# SCH_Szachy_2025-08-29.net
KiCad netlist of a schematic drawn in EasyEDA
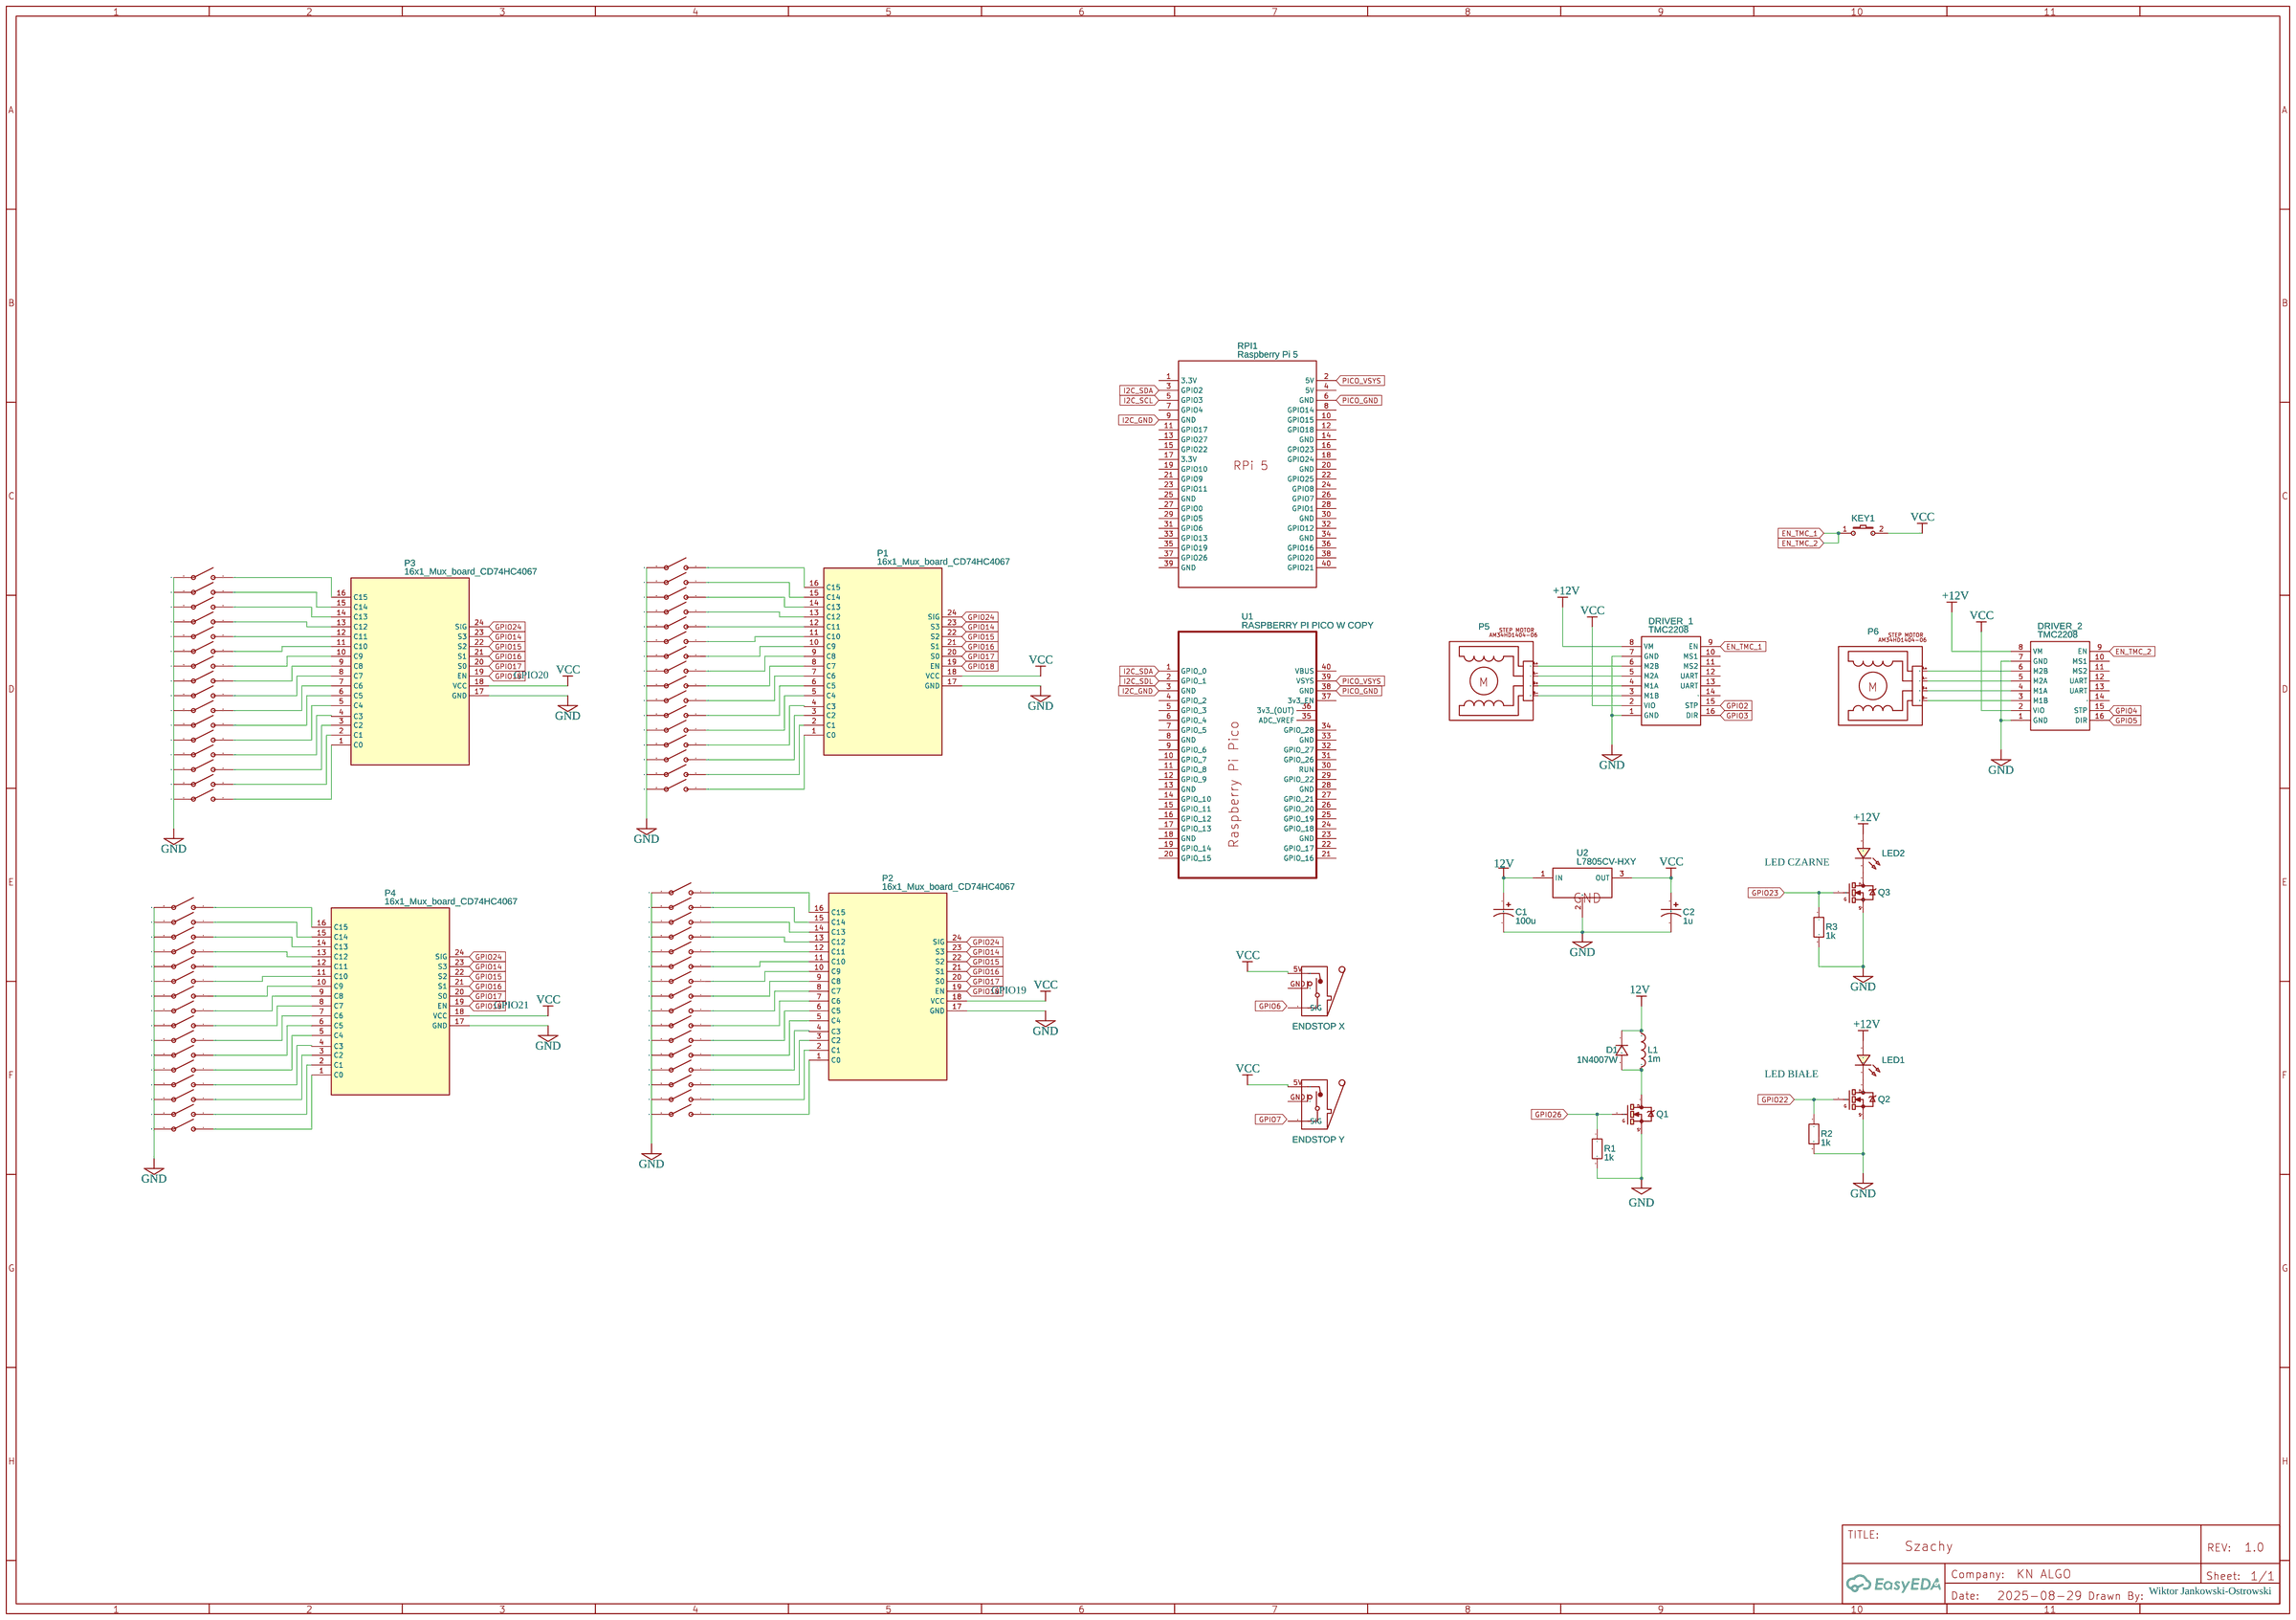
[diagram p0: schematic sheet]

(export (version "E")
  (design (tool "Eeschema 10.0.6"))
  (components
    (comp (ref "C1") (value "100u") (libsource (lib "") (part "C_Tan_SMD_A_US")))
    (comp (ref "C2") (value "1u") (libsource (lib "") (part "C_Tan_SMD_A_US")))
    (comp (ref "D1")
      (value "1N4007W")
      (fields (field (name "Manufacturer") "BLUE ROCKET"))
      (libsource (lib "") (part "1N4007W"))
    )
    (comp (ref "DIP1")
      (value "switch1")
      (fields (field (name "Manufacturer Part") "DIP switchEI-08") (field (name "Manufacturer") "DIP"))
      (libsource (lib "") (part "switch1"))
    )
    (comp (ref "DIP2")
      (value "switch1")
      (fields (field (name "Manufacturer Part") "DIP switchEI-08") (field (name "Manufacturer") "DIP"))
      (libsource (lib "") (part "switch1"))
    )
    (comp (ref "DIP3")
      (value "switch1")
      (fields (field (name "Manufacturer Part") "DIP switchEI-08") (field (name "Manufacturer") "DIP"))
      (libsource (lib "") (part "switch1"))
    )
    (comp (ref "DIP4")
      (value "switch1")
      (fields (field (name "Manufacturer Part") "DIP switchEI-08") (field (name "Manufacturer") "DIP"))
      (libsource (lib "") (part "switch1"))
    )
    (comp (ref "DIP5")
      (value "switch1")
      (fields (field (name "Manufacturer Part") "DIP switchEI-08") (field (name "Manufacturer") "DIP"))
      (libsource (lib "") (part "switch1"))
    )
    (comp (ref "DIP6")
      (value "switch1")
      (fields (field (name "Manufacturer Part") "DIP switchEI-08") (field (name "Manufacturer") "DIP"))
      (libsource (lib "") (part "switch1"))
    )
    (comp (ref "DIP7")
      (value "switch1")
      (fields (field (name "Manufacturer Part") "DIP switchEI-08") (field (name "Manufacturer") "DIP"))
      (libsource (lib "") (part "switch1"))
    )
    (comp (ref "DIP8")
      (value "switch1")
      (fields (field (name "Manufacturer Part") "DIP switchEI-08") (field (name "Manufacturer") "DIP"))
      (libsource (lib "") (part "switch1"))
    )
    (comp (ref "DIP9")
      (value "switch1")
      (fields (field (name "Manufacturer Part") "DIP switchEI-08") (field (name "Manufacturer") "DIP"))
      (libsource (lib "") (part "switch1"))
    )
    (comp (ref "DIP10")
      (value "switch1")
      (fields (field (name "Manufacturer Part") "DIP switchEI-08") (field (name "Manufacturer") "DIP"))
      (libsource (lib "") (part "switch1"))
    )
    (comp (ref "DIP11")
      (value "switch1")
      (fields (field (name "Manufacturer Part") "DIP switchEI-08") (field (name "Manufacturer") "DIP"))
      (libsource (lib "") (part "switch1"))
    )
    (comp (ref "DIP12")
      (value "switch1")
      (fields (field (name "Manufacturer Part") "DIP switchEI-08") (field (name "Manufacturer") "DIP"))
      (libsource (lib "") (part "switch1"))
    )
    (comp (ref "DIP13")
      (value "switch1")
      (fields (field (name "Manufacturer Part") "DIP switchEI-08") (field (name "Manufacturer") "DIP"))
      (libsource (lib "") (part "switch1"))
    )
    (comp (ref "DIP14")
      (value "switch1")
      (fields (field (name "Manufacturer Part") "DIP switchEI-08") (field (name "Manufacturer") "DIP"))
      (libsource (lib "") (part "switch1"))
    )
    (comp (ref "DIP15")
      (value "switch1")
      (fields (field (name "Manufacturer Part") "DIP switchEI-08") (field (name "Manufacturer") "DIP"))
      (libsource (lib "") (part "switch1"))
    )
    (comp (ref "DIP16")
      (value "switch1")
      (fields (field (name "Manufacturer Part") "DIP switchEI-08") (field (name "Manufacturer") "DIP"))
      (libsource (lib "") (part "switch1"))
    )
    (comp (ref "DIP17")
      (value "switch1")
      (fields (field (name "Manufacturer Part") "DIP switchEI-08") (field (name "Manufacturer") "DIP"))
      (libsource (lib "") (part "switch1"))
    )
    (comp (ref "DIP18")
      (value "switch1")
      (fields (field (name "Manufacturer Part") "DIP switchEI-08") (field (name "Manufacturer") "DIP"))
      (libsource (lib "") (part "switch1"))
    )
    (comp (ref "DIP19")
      (value "switch1")
      (fields (field (name "Manufacturer Part") "DIP switchEI-08") (field (name "Manufacturer") "DIP"))
      (libsource (lib "") (part "switch1"))
    )
    (comp (ref "DIP20")
      (value "switch1")
      (fields (field (name "Manufacturer Part") "DIP switchEI-08") (field (name "Manufacturer") "DIP"))
      (libsource (lib "") (part "switch1"))
    )
    (comp (ref "DIP21")
      (value "switch1")
      (fields (field (name "Manufacturer Part") "DIP switchEI-08") (field (name "Manufacturer") "DIP"))
      (libsource (lib "") (part "switch1"))
    )
    (comp (ref "DIP22")
      (value "switch1")
      (fields (field (name "Manufacturer Part") "DIP switchEI-08") (field (name "Manufacturer") "DIP"))
      (libsource (lib "") (part "switch1"))
    )
    (comp (ref "DIP23")
      (value "switch1")
      (fields (field (name "Manufacturer Part") "DIP switchEI-08") (field (name "Manufacturer") "DIP"))
      (libsource (lib "") (part "switch1"))
    )
    (comp (ref "DIP24")
      (value "switch1")
      (fields (field (name "Manufacturer Part") "DIP switchEI-08") (field (name "Manufacturer") "DIP"))
      (libsource (lib "") (part "switch1"))
    )
    (comp (ref "DIP25")
      (value "switch1")
      (fields (field (name "Manufacturer Part") "DIP switchEI-08") (field (name "Manufacturer") "DIP"))
      (libsource (lib "") (part "switch1"))
    )
    (comp (ref "DIP26")
      (value "switch1")
      (fields (field (name "Manufacturer Part") "DIP switchEI-08") (field (name "Manufacturer") "DIP"))
      (libsource (lib "") (part "switch1"))
    )
    (comp (ref "DIP27")
      (value "switch1")
      (fields (field (name "Manufacturer Part") "DIP switchEI-08") (field (name "Manufacturer") "DIP"))
      (libsource (lib "") (part "switch1"))
    )
    (comp (ref "DIP28")
      (value "switch1")
      (fields (field (name "Manufacturer Part") "DIP switchEI-08") (field (name "Manufacturer") "DIP"))
      (libsource (lib "") (part "switch1"))
    )
    (comp (ref "DIP29")
      (value "switch1")
      (fields (field (name "Manufacturer Part") "DIP switchEI-08") (field (name "Manufacturer") "DIP"))
      (libsource (lib "") (part "switch1"))
    )
    (comp (ref "DIP30")
      (value "switch1")
      (fields (field (name "Manufacturer Part") "DIP switchEI-08") (field (name "Manufacturer") "DIP"))
      (libsource (lib "") (part "switch1"))
    )
    (comp (ref "DIP31")
      (value "switch1")
      (fields (field (name "Manufacturer Part") "DIP switchEI-08") (field (name "Manufacturer") "DIP"))
      (libsource (lib "") (part "switch1"))
    )
    (comp (ref "DIP32")
      (value "switch1")
      (fields (field (name "Manufacturer Part") "DIP switchEI-08") (field (name "Manufacturer") "DIP"))
      (libsource (lib "") (part "switch1"))
    )
    (comp (ref "DIP33")
      (value "switch1")
      (fields (field (name "Manufacturer Part") "DIP switchEI-08") (field (name "Manufacturer") "DIP"))
      (libsource (lib "") (part "switch1"))
    )
    (comp (ref "DIP34")
      (value "switch1")
      (fields (field (name "Manufacturer Part") "DIP switchEI-08") (field (name "Manufacturer") "DIP"))
      (libsource (lib "") (part "switch1"))
    )
    (comp (ref "DIP35")
      (value "switch1")
      (fields (field (name "Manufacturer Part") "DIP switchEI-08") (field (name "Manufacturer") "DIP"))
      (libsource (lib "") (part "switch1"))
    )
    (comp (ref "DIP36")
      (value "switch1")
      (fields (field (name "Manufacturer Part") "DIP switchEI-08") (field (name "Manufacturer") "DIP"))
      (libsource (lib "") (part "switch1"))
    )
    (comp (ref "DIP37")
      (value "switch1")
      (fields (field (name "Manufacturer Part") "DIP switchEI-08") (field (name "Manufacturer") "DIP"))
      (libsource (lib "") (part "switch1"))
    )
    (comp (ref "DIP38")
      (value "switch1")
      (fields (field (name "Manufacturer Part") "DIP switchEI-08") (field (name "Manufacturer") "DIP"))
      (libsource (lib "") (part "switch1"))
    )
    (comp (ref "DIP39")
      (value "switch1")
      (fields (field (name "Manufacturer Part") "DIP switchEI-08") (field (name "Manufacturer") "DIP"))
      (libsource (lib "") (part "switch1"))
    )
    (comp (ref "DIP40")
      (value "switch1")
      (fields (field (name "Manufacturer Part") "DIP switchEI-08") (field (name "Manufacturer") "DIP"))
      (libsource (lib "") (part "switch1"))
    )
    (comp (ref "DIP41")
      (value "switch1")
      (fields (field (name "Manufacturer Part") "DIP switchEI-08") (field (name "Manufacturer") "DIP"))
      (libsource (lib "") (part "switch1"))
    )
    (comp (ref "DIP42")
      (value "switch1")
      (fields (field (name "Manufacturer Part") "DIP switchEI-08") (field (name "Manufacturer") "DIP"))
      (libsource (lib "") (part "switch1"))
    )
    (comp (ref "DIP43")
      (value "switch1")
      (fields (field (name "Manufacturer Part") "DIP switchEI-08") (field (name "Manufacturer") "DIP"))
      (libsource (lib "") (part "switch1"))
    )
    (comp (ref "DIP44")
      (value "switch1")
      (fields (field (name "Manufacturer Part") "DIP switchEI-08") (field (name "Manufacturer") "DIP"))
      (libsource (lib "") (part "switch1"))
    )
    (comp (ref "DIP45")
      (value "switch1")
      (fields (field (name "Manufacturer Part") "DIP switchEI-08") (field (name "Manufacturer") "DIP"))
      (libsource (lib "") (part "switch1"))
    )
    (comp (ref "DIP46")
      (value "switch1")
      (fields (field (name "Manufacturer Part") "DIP switchEI-08") (field (name "Manufacturer") "DIP"))
      (libsource (lib "") (part "switch1"))
    )
    (comp (ref "DIP47")
      (value "switch1")
      (fields (field (name "Manufacturer Part") "DIP switchEI-08") (field (name "Manufacturer") "DIP"))
      (libsource (lib "") (part "switch1"))
    )
    (comp (ref "DIP48")
      (value "switch1")
      (fields (field (name "Manufacturer Part") "DIP switchEI-08") (field (name "Manufacturer") "DIP"))
      (libsource (lib "") (part "switch1"))
    )
    (comp (ref "DIP49")
      (value "switch1")
      (fields (field (name "Manufacturer Part") "DIP switchEI-08") (field (name "Manufacturer") "DIP"))
      (libsource (lib "") (part "switch1"))
    )
    (comp (ref "DIP50")
      (value "switch1")
      (fields (field (name "Manufacturer Part") "DIP switchEI-08") (field (name "Manufacturer") "DIP"))
      (libsource (lib "") (part "switch1"))
    )
    (comp (ref "DIP51")
      (value "switch1")
      (fields (field (name "Manufacturer Part") "DIP switchEI-08") (field (name "Manufacturer") "DIP"))
      (libsource (lib "") (part "switch1"))
    )
    (comp (ref "DIP52")
      (value "switch1")
      (fields (field (name "Manufacturer Part") "DIP switchEI-08") (field (name "Manufacturer") "DIP"))
      (libsource (lib "") (part "switch1"))
    )
    (comp (ref "DIP53")
      (value "switch1")
      (fields (field (name "Manufacturer Part") "DIP switchEI-08") (field (name "Manufacturer") "DIP"))
      (libsource (lib "") (part "switch1"))
    )
    (comp (ref "DIP54")
      (value "switch1")
      (fields (field (name "Manufacturer Part") "DIP switchEI-08") (field (name "Manufacturer") "DIP"))
      (libsource (lib "") (part "switch1"))
    )
    (comp (ref "DIP55")
      (value "switch1")
      (fields (field (name "Manufacturer Part") "DIP switchEI-08") (field (name "Manufacturer") "DIP"))
      (libsource (lib "") (part "switch1"))
    )
    (comp (ref "DIP56")
      (value "switch1")
      (fields (field (name "Manufacturer Part") "DIP switchEI-08") (field (name "Manufacturer") "DIP"))
      (libsource (lib "") (part "switch1"))
    )
    (comp (ref "DIP57")
      (value "switch1")
      (fields (field (name "Manufacturer Part") "DIP switchEI-08") (field (name "Manufacturer") "DIP"))
      (libsource (lib "") (part "switch1"))
    )
    (comp (ref "DIP58")
      (value "switch1")
      (fields (field (name "Manufacturer Part") "DIP switchEI-08") (field (name "Manufacturer") "DIP"))
      (libsource (lib "") (part "switch1"))
    )
    (comp (ref "DIP59")
      (value "switch1")
      (fields (field (name "Manufacturer Part") "DIP switchEI-08") (field (name "Manufacturer") "DIP"))
      (libsource (lib "") (part "switch1"))
    )
    (comp (ref "DIP60")
      (value "switch1")
      (fields (field (name "Manufacturer Part") "DIP switchEI-08") (field (name "Manufacturer") "DIP"))
      (libsource (lib "") (part "switch1"))
    )
    (comp (ref "DIP61")
      (value "switch1")
      (fields (field (name "Manufacturer Part") "DIP switchEI-08") (field (name "Manufacturer") "DIP"))
      (libsource (lib "") (part "switch1"))
    )
    (comp (ref "DIP62")
      (value "switch1")
      (fields (field (name "Manufacturer Part") "DIP switchEI-08") (field (name "Manufacturer") "DIP"))
      (libsource (lib "") (part "switch1"))
    )
    (comp (ref "DIP63")
      (value "switch1")
      (fields (field (name "Manufacturer Part") "DIP switchEI-08") (field (name "Manufacturer") "DIP"))
      (libsource (lib "") (part "switch1"))
    )
    (comp (ref "DIP64")
      (value "switch1")
      (fields (field (name "Manufacturer Part") "DIP switchEI-08") (field (name "Manufacturer") "DIP"))
      (libsource (lib "") (part "switch1"))
    )
    (comp (ref "DRIVER_1") (value "TMC2208") (libsource (lib "") (part "TMC2208")))
    (comp (ref "DRIVER_2") (value "TMC2208") (libsource (lib "") (part "TMC2208")))
    (comp (ref "ESTP_FU1") (value "ENDSTOP X") (libsource (lib "") (part "EndStop")))
    (comp (ref "ESTP_FU2") (value "ENDSTOP Y") (libsource (lib "") (part "EndStop")))
    (comp (ref "KEY1")
      (value "K2-3.6×6.1_SMD")
      (fields (field (name "Manufacturer Part") "K2-1107ST-A4SW-06"))
      (libsource (lib "") (part "K2-3.6×6.1_SMD"))
    )
    (comp (ref "L1") (value "1m") (libsource (lib "") (part "L0603_US")))
    (comp (ref "LED1")
      (value "LED-0603_R")
      (fields
        (field (name "Manufacturer Part") "19-217/R6C-AL1M2VY/3T")
        (field (name "Manufacturer") "EVERLIGHT(台湾亿光)")
      )
      (libsource (lib "") (part "LED-0603_R"))
    )
    (comp (ref "LED2")
      (value "LED-0603_R")
      (fields
        (field (name "Manufacturer Part") "19-217/R6C-AL1M2VY/3T")
        (field (name "Manufacturer") "EVERLIGHT(台湾亿光)")
      )
      (libsource (lib "") (part "LED-0603_R"))
    )
    (comp (ref "P1")
      (value "16x1_Mux_board_CD74HC4067")
      (libsource (lib "") (part "16x1_Mux_board_CD74HC4067"))
    )
    (comp (ref "P2")
      (value "16x1_Mux_board_CD74HC4067")
      (libsource (lib "") (part "16x1_Mux_board_CD74HC4067"))
    )
    (comp (ref "P3")
      (value "16x1_Mux_board_CD74HC4067")
      (libsource (lib "") (part "16x1_Mux_board_CD74HC4067"))
    )
    (comp (ref "P4")
      (value "16x1_Mux_board_CD74HC4067")
      (libsource (lib "") (part "16x1_Mux_board_CD74HC4067"))
    )
    (comp (ref "P5")
      (value "STEPPER MOTOR AM34HD1404-06")
      (fields
        (field (name "Manufacturer Part") "Header-Male-2.54_1x6")
        (field (name "Manufacturer") "BOOMELE")
      )
      (libsource (lib "") (part "STEPPER MOTOR AM34HD1404-06"))
    )
    (comp (ref "P6")
      (value "STEPPER MOTOR AM34HD1404-06")
      (fields
        (field (name "Manufacturer Part") "Header-Male-2.54_1x6")
        (field (name "Manufacturer") "BOOMELE")
      )
      (libsource (lib "") (part "STEPPER MOTOR AM34HD1404-06"))
    )
    (comp (ref "Q1") (value "MOSFET-NCHANNELFDD8780") (libsource (lib "") (part "MOSFET-NCHANNELFDD8780")))
    (comp (ref "Q2") (value "MOSFET-NCHANNELFDD8780") (libsource (lib "") (part "MOSFET-NCHANNELFDD8780")))
    (comp (ref "Q3") (value "MOSFET-NCHANNELFDD8780") (libsource (lib "") (part "MOSFET-NCHANNELFDD8780")))
    (comp (ref "R1") (value "1k") (libsource (lib "") (part "R_0603_EU")))
    (comp (ref "R2") (value "1k") (libsource (lib "") (part "R_0603_EU")))
    (comp (ref "R3") (value "1k") (libsource (lib "") (part "R_0603_EU")))
    (comp (ref "RPI1")
      (value "Raspberry Pi 5")
      (fields (field (name "Manufacturer") "Raspberry Pi 5 4GB"))
      (libsource (lib "") (part "Raspberry Pi 5"))
    )
    (comp (ref "U1")
      (value "RASPBERRY PI PICO W COPY")
      (libsource (lib "") (part "RASPBERRY PI PICO W COPY"))
    )
    (comp (ref "U2")
      (value "L7805CV-HXY")
      (fields (field (name "Manufacturer") "HXY MOSFET(华轩阳电子)"))
      (libsource (lib "") (part "L7805CV-HXY"))
    )
  )
  (nets
    (net (code "1") (name "+12V") (class "Default")
      (node (ref "DRIVER_1") (pin "8") (pinfunction "VM_8") (pintype "unspecified"))
      (node (ref "DRIVER_2") (pin "8") (pinfunction "VM_8") (pintype "unspecified"))
      (node (ref "LED1") (pin "1") (pinfunction "1_1") (pintype "unspecified"))
      (node (ref "LED2") (pin "1") (pinfunction "1_1") (pintype "unspecified"))
    )
    (net (code "2") (name "12V") (class "Default")
      (node (ref "C1") (pin "1") (pinfunction "1_1") (pintype "unspecified"))
      (node (ref "D1") (pin "1") (pinfunction "1_1") (pintype "unspecified"))
      (node (ref "L1") (pin "1") (pinfunction "1_1") (pintype "unspecified"))
      (node (ref "U2") (pin "1") (pinfunction "IN_1") (pintype "passive"))
    )
    (net (code "3") (name "EN_TMC_1") (class "Default")
      (node (ref "DRIVER_1") (pin "9") (pinfunction "EN_9") (pintype "unspecified"))
      (node (ref "DRIVER_2") (pin "9") (pinfunction "EN_9") (pintype "unspecified"))
      (node (ref "KEY1") (pin "1") (pinfunction "1_1") (pintype "unspecified"))
    )
    (net (code "4") (name "GND") (class "Default")
      (node (ref "C1") (pin "2") (pinfunction "2_2") (pintype "unspecified"))
      (node (ref "C2") (pin "2") (pinfunction "2_2") (pintype "unspecified"))
      (node (ref "DRIVER_1") (pin "1") (pinfunction "GND_1") (pintype "unspecified"))
      (node (ref "DRIVER_1") (pin "7") (pinfunction "GND_7") (pintype "unspecified"))
      (node (ref "DRIVER_2") (pin "1") (pinfunction "GND_1") (pintype "unspecified"))
      (node (ref "DRIVER_2") (pin "7") (pinfunction "GND_7") (pintype "unspecified"))
      (node (ref "P1") (pin "17") (pinfunction "GND_17") (pintype "unspecified"))
      (node (ref "P2") (pin "17") (pinfunction "GND_17") (pintype "unspecified"))
      (node (ref "P3") (pin "17") (pinfunction "GND_17") (pintype "unspecified"))
      (node (ref "P4") (pin "17") (pinfunction "GND_17") (pintype "unspecified"))
      (node (ref "Q1") (pin "3") (pinfunction "S_3") (pintype "unspecified"))
      (node (ref "Q2") (pin "3") (pinfunction "S_3") (pintype "unspecified"))
      (node (ref "Q3") (pin "3") (pinfunction "S_3") (pintype "unspecified"))
      (node (ref "R1") (pin "2") (pinfunction "2_2") (pintype "unspecified"))
      (node (ref "R2") (pin "2") (pinfunction "2_2") (pintype "unspecified"))
      (node (ref "R3") (pin "2") (pinfunction "2_2") (pintype "unspecified"))
      (node (ref "U2") (pin "2") (pinfunction "GND_2") (pintype "passive"))
    )
    (net (code "5") (name "GPIO2") (class "Default")
      (node (ref "DRIVER_1") (pin "15") (pinfunction "STP_15") (pintype "unspecified"))
    )
    (net (code "6") (name "GPIO3") (class "Default")
      (node (ref "DRIVER_1") (pin "16") (pinfunction "DIR_16") (pintype "unspecified"))
    )
    (net (code "7") (name "GPIO4") (class "Default")
      (node (ref "DRIVER_2") (pin "15") (pinfunction "STP_15") (pintype "unspecified"))
    )
    (net (code "8") (name "GPIO5") (class "Default")
      (node (ref "DRIVER_2") (pin "16") (pinfunction "DIR_16") (pintype "unspecified"))
    )
    (net (code "11") (name "GPIO14") (class "Default")
      (node (ref "P1") (pin "23") (pinfunction "S3_23") (pintype "unspecified"))
      (node (ref "P2") (pin "23") (pinfunction "S3_23") (pintype "unspecified"))
      (node (ref "P3") (pin "23") (pinfunction "S3_23") (pintype "unspecified"))
      (node (ref "P4") (pin "23") (pinfunction "S3_23") (pintype "unspecified"))
    )
    (net (code "12") (name "GPIO15") (class "Default")
      (node (ref "P1") (pin "22") (pinfunction "S2_22") (pintype "unspecified"))
      (node (ref "P2") (pin "22") (pinfunction "S2_22") (pintype "unspecified"))
      (node (ref "P3") (pin "22") (pinfunction "S2_22") (pintype "unspecified"))
      (node (ref "P4") (pin "22") (pinfunction "S2_22") (pintype "unspecified"))
    )
    (net (code "13") (name "GPIO16") (class "Default")
      (node (ref "P1") (pin "21") (pinfunction "S1_21") (pintype "unspecified"))
      (node (ref "P2") (pin "21") (pinfunction "S1_21") (pintype "unspecified"))
      (node (ref "P3") (pin "21") (pinfunction "S1_21") (pintype "unspecified"))
      (node (ref "P4") (pin "21") (pinfunction "S1_21") (pintype "unspecified"))
    )
    (net (code "14") (name "GPIO17") (class "Default")
      (node (ref "P1") (pin "20") (pinfunction "S0_20") (pintype "unspecified"))
      (node (ref "P2") (pin "20") (pinfunction "S0_20") (pintype "unspecified"))
      (node (ref "P3") (pin "20") (pinfunction "S0_20") (pintype "unspecified"))
      (node (ref "P4") (pin "20") (pinfunction "S0_20") (pintype "unspecified"))
    )
    (net (code "15") (name "GPIO18") (class "Default")
      (node (ref "P1") (pin "19") (pinfunction "EN_19") (pintype "unspecified"))
      (node (ref "P2") (pin "19") (pinfunction "EN_19") (pintype "unspecified"))
      (node (ref "P3") (pin "19") (pinfunction "EN_19") (pintype "unspecified"))
      (node (ref "P4") (pin "19") (pinfunction "EN_19") (pintype "unspecified"))
    )
    (net (code "16") (name "GPIO22") (class "Default")
      (node (ref "Q2") (pin "1") (pinfunction "G_1") (pintype "unspecified"))
      (node (ref "R2") (pin "1") (pinfunction "1_1") (pintype "unspecified"))
    )
    (net (code "17") (name "GPIO23") (class "Default")
      (node (ref "Q3") (pin "1") (pinfunction "G_1") (pintype "unspecified"))
      (node (ref "R3") (pin "1") (pinfunction "1_1") (pintype "unspecified"))
    )
    (net (code "18") (name "GPIO24") (class "Default")
      (node (ref "P1") (pin "24") (pinfunction "SIG_24") (pintype "unspecified"))
      (node (ref "P2") (pin "24") (pinfunction "SIG_24") (pintype "unspecified"))
      (node (ref "P3") (pin "24") (pinfunction "SIG_24") (pintype "unspecified"))
      (node (ref "P4") (pin "24") (pinfunction "SIG_24") (pintype "unspecified"))
    )
    (net (code "19") (name "GPIO26") (class "Default")
      (node (ref "Q1") (pin "1") (pinfunction "G_1") (pintype "unspecified"))
      (node (ref "R1") (pin "1") (pinfunction "1_1") (pintype "unspecified"))
    )
    (net (code "20") (name "I2C_GND") (class "Default")
      (node (ref "RPI1") (pin "9") (pinfunction "GND_9") (pintype "unspecified"))
      (node (ref "U1") (pin "3") (pinfunction "GND_3") (pintype "unspecified"))
    )
    (net (code "21") (name "I2C_SCL") (class "Default")
      (node (ref "RPI1") (pin "5") (pinfunction "GPIO3_5") (pintype "bidirectional"))
    )
    (net (code "22") (name "I2C_SDA") (class "Default")
      (node (ref "RPI1") (pin "3") (pinfunction "GPIO2_3") (pintype "bidirectional"))
      (node (ref "U1") (pin "1") (pinfunction "GPIO_0_1") (pintype "unspecified"))
    )
    (net (code "23") (name "I2C_SDL") (class "Default")
      (node (ref "U1") (pin "2") (pinfunction "GPIO_1_2") (pintype "unspecified"))
    )
    (net (code "24") (name "Net-(DRIVER_1-M1A)") (class "Default")
      (node (ref "DRIVER_1") (pin "4") (pinfunction "M1A_4") (pintype "unspecified"))
      (node (ref "P5") (pin "B+") (pinfunction "B+_B+") (pintype "unspecified"))
    )
    (net (code "25") (name "Net-(DRIVER_1-M1B)") (class "Default")
      (node (ref "DRIVER_1") (pin "3") (pinfunction "M1B_3") (pintype "unspecified"))
      (node (ref "P5") (pin "B-") (pinfunction "B-_B-") (pintype "unspecified"))
    )
    (net (code "26") (name "Net-(DRIVER_1-M2A)") (class "Default")
      (node (ref "DRIVER_1") (pin "5") (pinfunction "M2A_5") (pintype "unspecified"))
      (node (ref "P5") (pin "A-") (pinfunction "A-_A-") (pintype "unspecified"))
    )
    (net (code "27") (name "Net-(DRIVER_1-M2B)") (class "Default")
      (node (ref "DRIVER_1") (pin "6") (pinfunction "M2B_6") (pintype "unspecified"))
      (node (ref "P5") (pin "A+") (pinfunction "A+_A+") (pintype "unspecified"))
    )
    (net (code "28") (name "Net-(DRIVER_2-M1A)") (class "Default")
      (node (ref "DRIVER_2") (pin "4") (pinfunction "M1A_4") (pintype "unspecified"))
      (node (ref "P6") (pin "B+") (pinfunction "B+_B+") (pintype "unspecified"))
    )
    (net (code "29") (name "Net-(DRIVER_2-M1B)") (class "Default")
      (node (ref "DRIVER_2") (pin "3") (pinfunction "M1B_3") (pintype "unspecified"))
      (node (ref "P6") (pin "B-") (pinfunction "B-_B-") (pintype "unspecified"))
    )
    (net (code "30") (name "Net-(DRIVER_2-M2A)") (class "Default")
      (node (ref "DRIVER_2") (pin "5") (pinfunction "M2A_5") (pintype "unspecified"))
      (node (ref "P6") (pin "A-") (pinfunction "A-_A-") (pintype "unspecified"))
    )
    (net (code "31") (name "Net-(DRIVER_2-M2B)") (class "Default")
      (node (ref "DRIVER_2") (pin "6") (pinfunction "M2B_6") (pintype "unspecified"))
      (node (ref "P6") (pin "A+") (pinfunction "A+_A+") (pintype "unspecified"))
    )
    (net (code "32") (name "Net-(Q1-D)") (class "Default")
      (node (ref "D1") (pin "2") (pinfunction "2_2") (pintype "unspecified"))
      (node (ref "L1") (pin "2") (pinfunction "2_2") (pintype "unspecified"))
      (node (ref "Q1") (pin "4") (pinfunction "D_4") (pintype "unspecified"))
    )
    (net (code "33") (name "Net-(Q2-D)") (class "Default")
      (node (ref "LED1") (pin "2") (pinfunction "2_2") (pintype "unspecified"))
      (node (ref "Q2") (pin "4") (pinfunction "D_4") (pintype "unspecified"))
    )
    (net (code "34") (name "Net-(Q3-D)") (class "Default")
      (node (ref "LED2") (pin "2") (pinfunction "2_2") (pintype "unspecified"))
      (node (ref "Q3") (pin "4") (pinfunction "D_4") (pintype "unspecified"))
    )
    (net (code "35") (name "PICO_GND") (class "Default")
      (node (ref "RPI1") (pin "6") (pinfunction "GND_6") (pintype "unspecified"))
      (node (ref "U1") (pin "38") (pinfunction "GND_38") (pintype "unspecified"))
    )
    (net (code "36") (name "PICO_VSYS") (class "Default")
      (node (ref "RPI1") (pin "2") (pinfunction "5V_2") (pintype "passive"))
      (node (ref "U1") (pin "39") (pinfunction "VSYS_39") (pintype "unspecified"))
    )
    (net (code "37") (name "VCC") (class "Default")
      (node (ref "C2") (pin "1") (pinfunction "1_1") (pintype "unspecified"))
      (node (ref "DRIVER_1") (pin "2") (pinfunction "VIO_2") (pintype "unspecified"))
      (node (ref "DRIVER_2") (pin "2") (pinfunction "VIO_2") (pintype "unspecified"))
      (node (ref "ESTP_FU1") (pin "5V") (pinfunction "2_5V") (pintype "unspecified"))
      (node (ref "ESTP_FU2") (pin "5V") (pinfunction "2_5V") (pintype "unspecified"))
      (node (ref "KEY1") (pin "2") (pinfunction "2_2") (pintype "unspecified"))
      (node (ref "P1") (pin "18") (pinfunction "VCC_18") (pintype "unspecified"))
      (node (ref "P2") (pin "18") (pinfunction "VCC_18") (pintype "unspecified"))
      (node (ref "P3") (pin "18") (pinfunction "VCC_18") (pintype "unspecified"))
      (node (ref "P4") (pin "18") (pinfunction "VCC_18") (pintype "unspecified"))
      (node (ref "U2") (pin "3") (pinfunction "OUT_3") (pintype "passive"))
    )
    (net (code "38") (name "unconnected-(DIP1-Pad1)") (class "Default")
      (node (ref "DIP1") (pin "1") (pinfunction "1_1") (pintype "unspecified"))
    )
    (net (code "39") (name "unconnected-(DIP1-Pad2)") (class "Default")
      (node (ref "DIP1") (pin "2") (pinfunction "2_2") (pintype "unspecified"))
    )
    (net (code "40") (name "unconnected-(DIP2-Pad1)") (class "Default")
      (node (ref "DIP2") (pin "1") (pinfunction "1_1") (pintype "unspecified"))
    )
    (net (code "41") (name "unconnected-(DIP2-Pad2)") (class "Default")
      (node (ref "DIP2") (pin "2") (pinfunction "2_2") (pintype "unspecified"))
    )
    (net (code "42") (name "unconnected-(DIP3-Pad1)") (class "Default")
      (node (ref "DIP3") (pin "1") (pinfunction "1_1") (pintype "unspecified"))
    )
    (net (code "43") (name "unconnected-(DIP3-Pad2)") (class "Default")
      (node (ref "DIP3") (pin "2") (pinfunction "2_2") (pintype "unspecified"))
    )
    (net (code "44") (name "unconnected-(DIP4-Pad1)") (class "Default")
      (node (ref "DIP4") (pin "1") (pinfunction "1_1") (pintype "unspecified"))
    )
    (net (code "45") (name "unconnected-(DIP4-Pad2)") (class "Default")
      (node (ref "DIP4") (pin "2") (pinfunction "2_2") (pintype "unspecified"))
    )
    (net (code "46") (name "unconnected-(DIP5-Pad1)") (class "Default")
      (node (ref "DIP5") (pin "1") (pinfunction "1_1") (pintype "unspecified"))
    )
    (net (code "47") (name "unconnected-(DIP5-Pad2)") (class "Default")
      (node (ref "DIP5") (pin "2") (pinfunction "2_2") (pintype "unspecified"))
    )
    (net (code "48") (name "unconnected-(DIP6-Pad1)") (class "Default")
      (node (ref "DIP6") (pin "1") (pinfunction "1_1") (pintype "unspecified"))
    )
    (net (code "49") (name "unconnected-(DIP6-Pad2)") (class "Default")
      (node (ref "DIP6") (pin "2") (pinfunction "2_2") (pintype "unspecified"))
    )
    (net (code "50") (name "unconnected-(DIP7-Pad1)") (class "Default")
      (node (ref "DIP7") (pin "1") (pinfunction "1_1") (pintype "unspecified"))
    )
    (net (code "51") (name "unconnected-(DIP7-Pad2)") (class "Default")
      (node (ref "DIP7") (pin "2") (pinfunction "2_2") (pintype "unspecified"))
    )
    (net (code "52") (name "unconnected-(DIP8-Pad1)") (class "Default")
      (node (ref "DIP8") (pin "1") (pinfunction "1_1") (pintype "unspecified"))
    )
    (net (code "53") (name "unconnected-(DIP8-Pad2)") (class "Default")
      (node (ref "DIP8") (pin "2") (pinfunction "2_2") (pintype "unspecified"))
    )
    (net (code "54") (name "unconnected-(DIP9-Pad1)") (class "Default")
      (node (ref "DIP9") (pin "1") (pinfunction "1_1") (pintype "unspecified"))
    )
    (net (code "55") (name "unconnected-(DIP9-Pad2)") (class "Default")
      (node (ref "DIP9") (pin "2") (pinfunction "2_2") (pintype "unspecified"))
    )
    (net (code "56") (name "unconnected-(DIP10-Pad1)") (class "Default")
      (node (ref "DIP10") (pin "1") (pinfunction "1_1") (pintype "unspecified"))
    )
    (net (code "57") (name "unconnected-(DIP10-Pad2)") (class "Default")
      (node (ref "DIP10") (pin "2") (pinfunction "2_2") (pintype "unspecified"))
    )
    (net (code "58") (name "unconnected-(DIP11-Pad1)") (class "Default")
      (node (ref "DIP11") (pin "1") (pinfunction "1_1") (pintype "unspecified"))
    )
    (net (code "59") (name "unconnected-(DIP11-Pad2)") (class "Default")
      (node (ref "DIP11") (pin "2") (pinfunction "2_2") (pintype "unspecified"))
    )
    (net (code "60") (name "unconnected-(DIP12-Pad1)") (class "Default")
      (node (ref "DIP12") (pin "1") (pinfunction "1_1") (pintype "unspecified"))
    )
    (net (code "61") (name "unconnected-(DIP12-Pad2)") (class "Default")
      (node (ref "DIP12") (pin "2") (pinfunction "2_2") (pintype "unspecified"))
    )
    (net (code "62") (name "unconnected-(DIP13-Pad1)") (class "Default")
      (node (ref "DIP13") (pin "1") (pinfunction "1_1") (pintype "unspecified"))
    )
    (net (code "63") (name "unconnected-(DIP13-Pad2)") (class "Default")
      (node (ref "DIP13") (pin "2") (pinfunction "2_2") (pintype "unspecified"))
    )
    (net (code "64") (name "unconnected-(DIP14-Pad1)") (class "Default")
      (node (ref "DIP14") (pin "1") (pinfunction "1_1") (pintype "unspecified"))
    )
    (net (code "65") (name "unconnected-(DIP14-Pad2)") (class "Default")
      (node (ref "DIP14") (pin "2") (pinfunction "2_2") (pintype "unspecified"))
    )
    (net (code "66") (name "unconnected-(DIP15-Pad1)") (class "Default")
      (node (ref "DIP15") (pin "1") (pinfunction "1_1") (pintype "unspecified"))
    )
    (net (code "67") (name "unconnected-(DIP15-Pad2)") (class "Default")
      (node (ref "DIP15") (pin "2") (pinfunction "2_2") (pintype "unspecified"))
    )
    (net (code "68") (name "unconnected-(DIP16-Pad1)") (class "Default")
      (node (ref "DIP16") (pin "1") (pinfunction "1_1") (pintype "unspecified"))
    )
    (net (code "69") (name "unconnected-(DIP16-Pad2)") (class "Default")
      (node (ref "DIP16") (pin "2") (pinfunction "2_2") (pintype "unspecified"))
    )
    (net (code "70") (name "unconnected-(DIP17-Pad1)") (class "Default")
      (node (ref "DIP17") (pin "1") (pinfunction "1_1") (pintype "unspecified"))
    )
    (net (code "71") (name "unconnected-(DIP17-Pad2)") (class "Default")
      (node (ref "DIP17") (pin "2") (pinfunction "2_2") (pintype "unspecified"))
    )
    (net (code "72") (name "unconnected-(DIP18-Pad1)") (class "Default")
      (node (ref "DIP18") (pin "1") (pinfunction "1_1") (pintype "unspecified"))
    )
    (net (code "73") (name "unconnected-(DIP18-Pad2)") (class "Default")
      (node (ref "DIP18") (pin "2") (pinfunction "2_2") (pintype "unspecified"))
    )
    (net (code "74") (name "unconnected-(DIP19-Pad1)") (class "Default")
      (node (ref "DIP19") (pin "1") (pinfunction "1_1") (pintype "unspecified"))
    )
    (net (code "75") (name "unconnected-(DIP19-Pad2)") (class "Default")
      (node (ref "DIP19") (pin "2") (pinfunction "2_2") (pintype "unspecified"))
    )
    (net (code "76") (name "unconnected-(DIP20-Pad1)") (class "Default")
      (node (ref "DIP20") (pin "1") (pinfunction "1_1") (pintype "unspecified"))
    )
    (net (code "77") (name "unconnected-(DIP20-Pad2)") (class "Default")
      (node (ref "DIP20") (pin "2") (pinfunction "2_2") (pintype "unspecified"))
    )
    (net (code "78") (name "unconnected-(DIP21-Pad1)") (class "Default")
      (node (ref "DIP21") (pin "1") (pinfunction "1_1") (pintype "unspecified"))
    )
    (net (code "79") (name "unconnected-(DIP21-Pad2)") (class "Default")
      (node (ref "DIP21") (pin "2") (pinfunction "2_2") (pintype "unspecified"))
    )
    (net (code "80") (name "unconnected-(DIP22-Pad1)") (class "Default")
      (node (ref "DIP22") (pin "1") (pinfunction "1_1") (pintype "unspecified"))
    )
    (net (code "81") (name "unconnected-(DIP22-Pad2)") (class "Default")
      (node (ref "DIP22") (pin "2") (pinfunction "2_2") (pintype "unspecified"))
    )
    (net (code "82") (name "unconnected-(DIP23-Pad1)") (class "Default")
      (node (ref "DIP23") (pin "1") (pinfunction "1_1") (pintype "unspecified"))
    )
    (net (code "83") (name "unconnected-(DIP23-Pad2)") (class "Default")
      (node (ref "DIP23") (pin "2") (pinfunction "2_2") (pintype "unspecified"))
    )
    (net (code "84") (name "unconnected-(DIP24-Pad1)") (class "Default")
      (node (ref "DIP24") (pin "1") (pinfunction "1_1") (pintype "unspecified"))
    )
    (net (code "85") (name "unconnected-(DIP24-Pad2)") (class "Default")
      (node (ref "DIP24") (pin "2") (pinfunction "2_2") (pintype "unspecified"))
    )
    (net (code "86") (name "unconnected-(DIP25-Pad1)") (class "Default")
      (node (ref "DIP25") (pin "1") (pinfunction "1_1") (pintype "unspecified"))
    )
    (net (code "87") (name "unconnected-(DIP25-Pad2)") (class "Default")
      (node (ref "DIP25") (pin "2") (pinfunction "2_2") (pintype "unspecified"))
    )
    (net (code "88") (name "unconnected-(DIP26-Pad1)") (class "Default")
      (node (ref "DIP26") (pin "1") (pinfunction "1_1") (pintype "unspecified"))
    )
    (net (code "89") (name "unconnected-(DIP26-Pad2)") (class "Default")
      (node (ref "DIP26") (pin "2") (pinfunction "2_2") (pintype "unspecified"))
    )
    (net (code "90") (name "unconnected-(DIP27-Pad1)") (class "Default")
      (node (ref "DIP27") (pin "1") (pinfunction "1_1") (pintype "unspecified"))
    )
    (net (code "91") (name "unconnected-(DIP27-Pad2)") (class "Default")
      (node (ref "DIP27") (pin "2") (pinfunction "2_2") (pintype "unspecified"))
    )
    (net (code "92") (name "unconnected-(DIP28-Pad1)") (class "Default")
      (node (ref "DIP28") (pin "1") (pinfunction "1_1") (pintype "unspecified"))
    )
    (net (code "93") (name "unconnected-(DIP28-Pad2)") (class "Default")
      (node (ref "DIP28") (pin "2") (pinfunction "2_2") (pintype "unspecified"))
    )
    (net (code "94") (name "unconnected-(DIP29-Pad1)") (class "Default")
      (node (ref "DIP29") (pin "1") (pinfunction "1_1") (pintype "unspecified"))
    )
    (net (code "95") (name "unconnected-(DIP29-Pad2)") (class "Default")
      (node (ref "DIP29") (pin "2") (pinfunction "2_2") (pintype "unspecified"))
    )
    (net (code "96") (name "unconnected-(DIP30-Pad1)") (class "Default")
      (node (ref "DIP30") (pin "1") (pinfunction "1_1") (pintype "unspecified"))
    )
    (net (code "97") (name "unconnected-(DIP30-Pad2)") (class "Default")
      (node (ref "DIP30") (pin "2") (pinfunction "2_2") (pintype "unspecified"))
    )
    (net (code "98") (name "unconnected-(DIP31-Pad1)") (class "Default")
      (node (ref "DIP31") (pin "1") (pinfunction "1_1") (pintype "unspecified"))
    )
    (net (code "99") (name "unconnected-(DIP31-Pad2)") (class "Default")
      (node (ref "DIP31") (pin "2") (pinfunction "2_2") (pintype "unspecified"))
    )
    (net (code "100") (name "unconnected-(DIP32-Pad1)") (class "Default")
      (node (ref "DIP32") (pin "1") (pinfunction "1_1") (pintype "unspecified"))
    )
    (net (code "101") (name "unconnected-(DIP32-Pad2)") (class "Default")
      (node (ref "DIP32") (pin "2") (pinfunction "2_2") (pintype "unspecified"))
    )
    (net (code "102") (name "unconnected-(DIP33-Pad1)") (class "Default")
      (node (ref "DIP33") (pin "1") (pinfunction "1_1") (pintype "unspecified"))
    )
    (net (code "103") (name "unconnected-(DIP33-Pad2)") (class "Default")
      (node (ref "DIP33") (pin "2") (pinfunction "2_2") (pintype "unspecified"))
    )
    (net (code "104") (name "unconnected-(DIP34-Pad1)") (class "Default")
      (node (ref "DIP34") (pin "1") (pinfunction "1_1") (pintype "unspecified"))
    )
    (net (code "105") (name "unconnected-(DIP34-Pad2)") (class "Default")
      (node (ref "DIP34") (pin "2") (pinfunction "2_2") (pintype "unspecified"))
    )
    (net (code "106") (name "unconnected-(DIP35-Pad1)") (class "Default")
      (node (ref "DIP35") (pin "1") (pinfunction "1_1") (pintype "unspecified"))
    )
    (net (code "107") (name "unconnected-(DIP35-Pad2)") (class "Default")
      (node (ref "DIP35") (pin "2") (pinfunction "2_2") (pintype "unspecified"))
    )
    (net (code "108") (name "unconnected-(DIP36-Pad1)") (class "Default")
      (node (ref "DIP36") (pin "1") (pinfunction "1_1") (pintype "unspecified"))
    )
    (net (code "109") (name "unconnected-(DIP36-Pad2)") (class "Default")
      (node (ref "DIP36") (pin "2") (pinfunction "2_2") (pintype "unspecified"))
    )
    (net (code "110") (name "unconnected-(DIP37-Pad1)") (class "Default")
      (node (ref "DIP37") (pin "1") (pinfunction "1_1") (pintype "unspecified"))
    )
    (net (code "111") (name "unconnected-(DIP37-Pad2)") (class "Default")
      (node (ref "DIP37") (pin "2") (pinfunction "2_2") (pintype "unspecified"))
    )
    (net (code "112") (name "unconnected-(DIP38-Pad1)") (class "Default")
      (node (ref "DIP38") (pin "1") (pinfunction "1_1") (pintype "unspecified"))
    )
    (net (code "113") (name "unconnected-(DIP38-Pad2)") (class "Default")
      (node (ref "DIP38") (pin "2") (pinfunction "2_2") (pintype "unspecified"))
    )
    (net (code "114") (name "unconnected-(DIP39-Pad1)") (class "Default")
      (node (ref "DIP39") (pin "1") (pinfunction "1_1") (pintype "unspecified"))
    )
    (net (code "115") (name "unconnected-(DIP39-Pad2)") (class "Default")
      (node (ref "DIP39") (pin "2") (pinfunction "2_2") (pintype "unspecified"))
    )
    (net (code "116") (name "unconnected-(DIP40-Pad1)") (class "Default")
      (node (ref "DIP40") (pin "1") (pinfunction "1_1") (pintype "unspecified"))
    )
    (net (code "117") (name "unconnected-(DIP40-Pad2)") (class "Default")
      (node (ref "DIP40") (pin "2") (pinfunction "2_2") (pintype "unspecified"))
    )
    (net (code "118") (name "unconnected-(DIP41-Pad1)") (class "Default")
      (node (ref "DIP41") (pin "1") (pinfunction "1_1") (pintype "unspecified"))
    )
    (net (code "119") (name "unconnected-(DIP41-Pad2)") (class "Default")
      (node (ref "DIP41") (pin "2") (pinfunction "2_2") (pintype "unspecified"))
    )
    (net (code "120") (name "unconnected-(DIP42-Pad1)") (class "Default")
      (node (ref "DIP42") (pin "1") (pinfunction "1_1") (pintype "unspecified"))
    )
    (net (code "121") (name "unconnected-(DIP42-Pad2)") (class "Default")
      (node (ref "DIP42") (pin "2") (pinfunction "2_2") (pintype "unspecified"))
    )
    (net (code "122") (name "unconnected-(DIP43-Pad1)") (class "Default")
      (node (ref "DIP43") (pin "1") (pinfunction "1_1") (pintype "unspecified"))
    )
    (net (code "123") (name "unconnected-(DIP43-Pad2)") (class "Default")
      (node (ref "DIP43") (pin "2") (pinfunction "2_2") (pintype "unspecified"))
    )
    (net (code "124") (name "unconnected-(DIP44-Pad1)") (class "Default")
      (node (ref "DIP44") (pin "1") (pinfunction "1_1") (pintype "unspecified"))
    )
    (net (code "125") (name "unconnected-(DIP44-Pad2)") (class "Default")
      (node (ref "DIP44") (pin "2") (pinfunction "2_2") (pintype "unspecified"))
    )
    (net (code "126") (name "unconnected-(DIP45-Pad1)") (class "Default")
      (node (ref "DIP45") (pin "1") (pinfunction "1_1") (pintype "unspecified"))
    )
    (net (code "127") (name "unconnected-(DIP45-Pad2)") (class "Default")
      (node (ref "DIP45") (pin "2") (pinfunction "2_2") (pintype "unspecified"))
    )
    (net (code "128") (name "unconnected-(DIP46-Pad1)") (class "Default")
      (node (ref "DIP46") (pin "1") (pinfunction "1_1") (pintype "unspecified"))
    )
    (net (code "129") (name "unconnected-(DIP46-Pad2)") (class "Default")
      (node (ref "DIP46") (pin "2") (pinfunction "2_2") (pintype "unspecified"))
    )
    (net (code "130") (name "unconnected-(DIP47-Pad1)") (class "Default")
      (node (ref "DIP47") (pin "1") (pinfunction "1_1") (pintype "unspecified"))
    )
    (net (code "131") (name "unconnected-(DIP47-Pad2)") (class "Default")
      (node (ref "DIP47") (pin "2") (pinfunction "2_2") (pintype "unspecified"))
    )
    (net (code "132") (name "unconnected-(DIP48-Pad1)") (class "Default")
      (node (ref "DIP48") (pin "1") (pinfunction "1_1") (pintype "unspecified"))
    )
    (net (code "133") (name "unconnected-(DIP48-Pad2)") (class "Default")
      (node (ref "DIP48") (pin "2") (pinfunction "2_2") (pintype "unspecified"))
    )
    (net (code "134") (name "unconnected-(DIP49-Pad1)") (class "Default")
      (node (ref "DIP49") (pin "1") (pinfunction "1_1") (pintype "unspecified"))
    )
    (net (code "135") (name "unconnected-(DIP49-Pad2)") (class "Default")
      (node (ref "DIP49") (pin "2") (pinfunction "2_2") (pintype "unspecified"))
    )
    (net (code "136") (name "unconnected-(DIP50-Pad1)") (class "Default")
      (node (ref "DIP50") (pin "1") (pinfunction "1_1") (pintype "unspecified"))
    )
    (net (code "137") (name "unconnected-(DIP50-Pad2)") (class "Default")
      (node (ref "DIP50") (pin "2") (pinfunction "2_2") (pintype "unspecified"))
    )
    (net (code "138") (name "unconnected-(DIP51-Pad1)") (class "Default")
      (node (ref "DIP51") (pin "1") (pinfunction "1_1") (pintype "unspecified"))
    )
    (net (code "139") (name "unconnected-(DIP51-Pad2)") (class "Default")
      (node (ref "DIP51") (pin "2") (pinfunction "2_2") (pintype "unspecified"))
    )
    (net (code "140") (name "unconnected-(DIP52-Pad1)") (class "Default")
      (node (ref "DIP52") (pin "1") (pinfunction "1_1") (pintype "unspecified"))
    )
    (net (code "141") (name "unconnected-(DIP52-Pad2)") (class "Default")
      (node (ref "DIP52") (pin "2") (pinfunction "2_2") (pintype "unspecified"))
    )
    (net (code "142") (name "unconnected-(DIP53-Pad1)") (class "Default")
      (node (ref "DIP53") (pin "1") (pinfunction "1_1") (pintype "unspecified"))
    )
    (net (code "143") (name "unconnected-(DIP53-Pad2)") (class "Default")
      (node (ref "DIP53") (pin "2") (pinfunction "2_2") (pintype "unspecified"))
    )
    (net (code "144") (name "unconnected-(DIP54-Pad1)") (class "Default")
      (node (ref "DIP54") (pin "1") (pinfunction "1_1") (pintype "unspecified"))
    )
    (net (code "145") (name "unconnected-(DIP54-Pad2)") (class "Default")
      (node (ref "DIP54") (pin "2") (pinfunction "2_2") (pintype "unspecified"))
    )
    (net (code "146") (name "unconnected-(DIP55-Pad1)") (class "Default")
      (node (ref "DIP55") (pin "1") (pinfunction "1_1") (pintype "unspecified"))
    )
    (net (code "147") (name "unconnected-(DIP55-Pad2)") (class "Default")
      (node (ref "DIP55") (pin "2") (pinfunction "2_2") (pintype "unspecified"))
    )
    (net (code "148") (name "unconnected-(DIP56-Pad1)") (class "Default")
      (node (ref "DIP56") (pin "1") (pinfunction "1_1") (pintype "unspecified"))
    )
    (net (code "149") (name "unconnected-(DIP56-Pad2)") (class "Default")
      (node (ref "DIP56") (pin "2") (pinfunction "2_2") (pintype "unspecified"))
    )
    (net (code "150") (name "unconnected-(DIP57-Pad1)") (class "Default")
      (node (ref "DIP57") (pin "1") (pinfunction "1_1") (pintype "unspecified"))
    )
    (net (code "151") (name "unconnected-(DIP57-Pad2)") (class "Default")
      (node (ref "DIP57") (pin "2") (pinfunction "2_2") (pintype "unspecified"))
    )
    (net (code "152") (name "unconnected-(DIP58-Pad1)") (class "Default")
      (node (ref "DIP58") (pin "1") (pinfunction "1_1") (pintype "unspecified"))
    )
    (net (code "153") (name "unconnected-(DIP58-Pad2)") (class "Default")
      (node (ref "DIP58") (pin "2") (pinfunction "2_2") (pintype "unspecified"))
    )
    (net (code "154") (name "unconnected-(DIP59-Pad1)") (class "Default")
      (node (ref "DIP59") (pin "1") (pinfunction "1_1") (pintype "unspecified"))
    )
    (net (code "155") (name "unconnected-(DIP59-Pad2)") (class "Default")
      (node (ref "DIP59") (pin "2") (pinfunction "2_2") (pintype "unspecified"))
    )
    (net (code "156") (name "unconnected-(DIP60-Pad1)") (class "Default")
      (node (ref "DIP60") (pin "1") (pinfunction "1_1") (pintype "unspecified"))
    )
    (net (code "157") (name "unconnected-(DIP60-Pad2)") (class "Default")
      (node (ref "DIP60") (pin "2") (pinfunction "2_2") (pintype "unspecified"))
    )
    (net (code "158") (name "unconnected-(DIP61-Pad1)") (class "Default")
      (node (ref "DIP61") (pin "1") (pinfunction "1_1") (pintype "unspecified"))
    )
    (net (code "159") (name "unconnected-(DIP61-Pad2)") (class "Default")
      (node (ref "DIP61") (pin "2") (pinfunction "2_2") (pintype "unspecified"))
    )
    (net (code "160") (name "unconnected-(DIP62-Pad1)") (class "Default")
      (node (ref "DIP62") (pin "1") (pinfunction "1_1") (pintype "unspecified"))
    )
    (net (code "161") (name "unconnected-(DIP62-Pad2)") (class "Default")
      (node (ref "DIP62") (pin "2") (pinfunction "2_2") (pintype "unspecified"))
    )
    (net (code "162") (name "unconnected-(DIP63-Pad1)") (class "Default")
      (node (ref "DIP63") (pin "1") (pinfunction "1_1") (pintype "unspecified"))
    )
    (net (code "163") (name "unconnected-(DIP63-Pad2)") (class "Default")
      (node (ref "DIP63") (pin "2") (pinfunction "2_2") (pintype "unspecified"))
    )
    (net (code "164") (name "unconnected-(DIP64-Pad1)") (class "Default")
      (node (ref "DIP64") (pin "1") (pinfunction "1_1") (pintype "unspecified"))
    )
    (net (code "165") (name "unconnected-(DIP64-Pad2)") (class "Default")
      (node (ref "DIP64") (pin "2") (pinfunction "2_2") (pintype "unspecified"))
    )
    (net (code "166") (name "unconnected-(DRIVER_1-6-Pad14)") (class "Default")
      (node (ref "DRIVER_1") (pin "14") (pinfunction "6_14") (pintype "unspecified"))
    )
    (net (code "167") (name "unconnected-(DRIVER_1-MS1-Pad10)") (class "Default")
      (node (ref "DRIVER_1") (pin "10") (pinfunction "MS1_10") (pintype "unspecified"))
    )
    (net (code "168") (name "unconnected-(DRIVER_1-MS2-Pad11)") (class "Default")
      (node (ref "DRIVER_1") (pin "11") (pinfunction "MS2_11") (pintype "unspecified"))
    )
    (net (code "169") (name "unconnected-(DRIVER_1-UART-Pad12)") (class "Default")
      (node (ref "DRIVER_1") (pin "12") (pinfunction "UART_12") (pintype "unspecified"))
    )
    (net (code "170") (name "unconnected-(DRIVER_1-UART-Pad13)") (class "Default")
      (node (ref "DRIVER_1") (pin "13") (pinfunction "UART_13") (pintype "unspecified"))
    )
    (net (code "171") (name "unconnected-(DRIVER_2-6-Pad14)") (class "Default")
      (node (ref "DRIVER_2") (pin "14") (pinfunction "6_14") (pintype "unspecified"))
    )
    (net (code "172") (name "unconnected-(DRIVER_2-MS1-Pad10)") (class "Default")
      (node (ref "DRIVER_2") (pin "10") (pinfunction "MS1_10") (pintype "unspecified"))
    )
    (net (code "173") (name "unconnected-(DRIVER_2-MS2-Pad11)") (class "Default")
      (node (ref "DRIVER_2") (pin "11") (pinfunction "MS2_11") (pintype "unspecified"))
    )
    (net (code "174") (name "unconnected-(DRIVER_2-UART-Pad12)") (class "Default")
      (node (ref "DRIVER_2") (pin "12") (pinfunction "UART_12") (pintype "unspecified"))
    )
    (net (code "175") (name "unconnected-(DRIVER_2-UART-Pad13)") (class "Default")
      (node (ref "DRIVER_2") (pin "13") (pinfunction "UART_13") (pintype "unspecified"))
    )
    (net (code "176") (name "unconnected-(ESTP_FU1-3-PadGND)") (class "Default")
      (node (ref "ESTP_FU1") (pin "GND") (pinfunction "3_GND") (pintype "unspecified"))
    )
    (net (code "177") (name "unconnected-(ESTP_FU1-SIG-Pad1)") (class "Default")
      (node (ref "ESTP_FU1") (pin "1") (pinfunction "SIG_1") (pintype "unspecified"))
    )
    (net (code "178") (name "unconnected-(ESTP_FU2-3-PadGND)") (class "Default")
      (node (ref "ESTP_FU2") (pin "GND") (pinfunction "3_GND") (pintype "unspecified"))
    )
    (net (code "179") (name "unconnected-(ESTP_FU2-SIG-Pad1)") (class "Default")
      (node (ref "ESTP_FU2") (pin "1") (pinfunction "SIG_1") (pintype "unspecified"))
    )
    (net (code "180") (name "unconnected-(P1-C0-Pad1)") (class "Default")
      (node (ref "P1") (pin "1") (pinfunction "C0_1") (pintype "unspecified"))
    )
    (net (code "181") (name "unconnected-(P1-C1-Pad2)") (class "Default")
      (node (ref "P1") (pin "2") (pinfunction "C1_2") (pintype "unspecified"))
    )
    (net (code "182") (name "unconnected-(P1-C2-Pad3)") (class "Default")
      (node (ref "P1") (pin "3") (pinfunction "C2_3") (pintype "unspecified"))
    )
    (net (code "183") (name "unconnected-(P1-C3-Pad4)") (class "Default")
      (node (ref "P1") (pin "4") (pinfunction "C3_4") (pintype "unspecified"))
    )
    (net (code "184") (name "unconnected-(P1-C4-Pad5)") (class "Default")
      (node (ref "P1") (pin "5") (pinfunction "C4_5") (pintype "unspecified"))
    )
    (net (code "185") (name "unconnected-(P1-C5-Pad6)") (class "Default")
      (node (ref "P1") (pin "6") (pinfunction "C5_6") (pintype "unspecified"))
    )
    (net (code "186") (name "unconnected-(P1-C6-Pad7)") (class "Default")
      (node (ref "P1") (pin "7") (pinfunction "C6_7") (pintype "unspecified"))
    )
    (net (code "187") (name "unconnected-(P1-C7-Pad8)") (class "Default")
      (node (ref "P1") (pin "8") (pinfunction "C7_8") (pintype "unspecified"))
    )
    (net (code "188") (name "unconnected-(P1-C8-Pad9)") (class "Default")
      (node (ref "P1") (pin "9") (pinfunction "C8_9") (pintype "unspecified"))
    )
    (net (code "189") (name "unconnected-(P1-C9-Pad10)") (class "Default")
      (node (ref "P1") (pin "10") (pinfunction "C9_10") (pintype "unspecified"))
    )
    (net (code "190") (name "unconnected-(P1-C10-Pad11)") (class "Default")
      (node (ref "P1") (pin "11") (pinfunction "C10_11") (pintype "unspecified"))
    )
    (net (code "191") (name "unconnected-(P1-C11-Pad12)") (class "Default")
      (node (ref "P1") (pin "12") (pinfunction "C11_12") (pintype "unspecified"))
    )
    (net (code "192") (name "unconnected-(P1-C12-Pad13)") (class "Default")
      (node (ref "P1") (pin "13") (pinfunction "C12_13") (pintype "unspecified"))
    )
    (net (code "193") (name "unconnected-(P1-C13-Pad14)") (class "Default")
      (node (ref "P1") (pin "14") (pinfunction "C13_14") (pintype "unspecified"))
    )
    (net (code "194") (name "unconnected-(P1-C14-Pad15)") (class "Default")
      (node (ref "P1") (pin "15") (pinfunction "C14_15") (pintype "unspecified"))
    )
    (net (code "195") (name "unconnected-(P1-C15-Pad16)") (class "Default")
      (node (ref "P1") (pin "16") (pinfunction "C15_16") (pintype "unspecified"))
    )
    (net (code "196") (name "unconnected-(P2-C0-Pad1)") (class "Default")
      (node (ref "P2") (pin "1") (pinfunction "C0_1") (pintype "unspecified"))
    )
    (net (code "197") (name "unconnected-(P2-C1-Pad2)") (class "Default")
      (node (ref "P2") (pin "2") (pinfunction "C1_2") (pintype "unspecified"))
    )
    (net (code "198") (name "unconnected-(P2-C2-Pad3)") (class "Default")
      (node (ref "P2") (pin "3") (pinfunction "C2_3") (pintype "unspecified"))
    )
    (net (code "199") (name "unconnected-(P2-C3-Pad4)") (class "Default")
      (node (ref "P2") (pin "4") (pinfunction "C3_4") (pintype "unspecified"))
    )
    (net (code "200") (name "unconnected-(P2-C4-Pad5)") (class "Default")
      (node (ref "P2") (pin "5") (pinfunction "C4_5") (pintype "unspecified"))
    )
    (net (code "201") (name "unconnected-(P2-C5-Pad6)") (class "Default")
      (node (ref "P2") (pin "6") (pinfunction "C5_6") (pintype "unspecified"))
    )
    (net (code "202") (name "unconnected-(P2-C6-Pad7)") (class "Default")
      (node (ref "P2") (pin "7") (pinfunction "C6_7") (pintype "unspecified"))
    )
    (net (code "203") (name "unconnected-(P2-C7-Pad8)") (class "Default")
      (node (ref "P2") (pin "8") (pinfunction "C7_8") (pintype "unspecified"))
    )
    (net (code "204") (name "unconnected-(P2-C8-Pad9)") (class "Default")
      (node (ref "P2") (pin "9") (pinfunction "C8_9") (pintype "unspecified"))
    )
    (net (code "205") (name "unconnected-(P2-C9-Pad10)") (class "Default")
      (node (ref "P2") (pin "10") (pinfunction "C9_10") (pintype "unspecified"))
    )
    (net (code "206") (name "unconnected-(P2-C10-Pad11)") (class "Default")
      (node (ref "P2") (pin "11") (pinfunction "C10_11") (pintype "unspecified"))
    )
    (net (code "207") (name "unconnected-(P2-C11-Pad12)") (class "Default")
      (node (ref "P2") (pin "12") (pinfunction "C11_12") (pintype "unspecified"))
    )
    (net (code "208") (name "unconnected-(P2-C12-Pad13)") (class "Default")
      (node (ref "P2") (pin "13") (pinfunction "C12_13") (pintype "unspecified"))
    )
    (net (code "209") (name "unconnected-(P2-C13-Pad14)") (class "Default")
      (node (ref "P2") (pin "14") (pinfunction "C13_14") (pintype "unspecified"))
    )
    (net (code "210") (name "unconnected-(P2-C14-Pad15)") (class "Default")
      (node (ref "P2") (pin "15") (pinfunction "C14_15") (pintype "unspecified"))
    )
    (net (code "211") (name "unconnected-(P2-C15-Pad16)") (class "Default")
      (node (ref "P2") (pin "16") (pinfunction "C15_16") (pintype "unspecified"))
    )
    (net (code "212") (name "unconnected-(P3-C0-Pad1)") (class "Default")
      (node (ref "P3") (pin "1") (pinfunction "C0_1") (pintype "unspecified"))
    )
    (net (code "213") (name "unconnected-(P3-C1-Pad2)") (class "Default")
      (node (ref "P3") (pin "2") (pinfunction "C1_2") (pintype "unspecified"))
    )
    (net (code "214") (name "unconnected-(P3-C2-Pad3)") (class "Default")
      (node (ref "P3") (pin "3") (pinfunction "C2_3") (pintype "unspecified"))
    )
    (net (code "215") (name "unconnected-(P3-C3-Pad4)") (class "Default")
      (node (ref "P3") (pin "4") (pinfunction "C3_4") (pintype "unspecified"))
    )
    (net (code "216") (name "unconnected-(P3-C4-Pad5)") (class "Default")
      (node (ref "P3") (pin "5") (pinfunction "C4_5") (pintype "unspecified"))
    )
    (net (code "217") (name "unconnected-(P3-C5-Pad6)") (class "Default")
      (node (ref "P3") (pin "6") (pinfunction "C5_6") (pintype "unspecified"))
    )
    (net (code "218") (name "unconnected-(P3-C6-Pad7)") (class "Default")
      (node (ref "P3") (pin "7") (pinfunction "C6_7") (pintype "unspecified"))
    )
    (net (code "219") (name "unconnected-(P3-C7-Pad8)") (class "Default")
      (node (ref "P3") (pin "8") (pinfunction "C7_8") (pintype "unspecified"))
    )
    (net (code "220") (name "unconnected-(P3-C8-Pad9)") (class "Default")
      (node (ref "P3") (pin "9") (pinfunction "C8_9") (pintype "unspecified"))
    )
    (net (code "221") (name "unconnected-(P3-C9-Pad10)") (class "Default")
      (node (ref "P3") (pin "10") (pinfunction "C9_10") (pintype "unspecified"))
    )
    (net (code "222") (name "unconnected-(P3-C10-Pad11)") (class "Default")
      (node (ref "P3") (pin "11") (pinfunction "C10_11") (pintype "unspecified"))
    )
    (net (code "223") (name "unconnected-(P3-C11-Pad12)") (class "Default")
      (node (ref "P3") (pin "12") (pinfunction "C11_12") (pintype "unspecified"))
    )
    (net (code "224") (name "unconnected-(P3-C12-Pad13)") (class "Default")
      (node (ref "P3") (pin "13") (pinfunction "C12_13") (pintype "unspecified"))
    )
    (net (code "225") (name "unconnected-(P3-C13-Pad14)") (class "Default")
      (node (ref "P3") (pin "14") (pinfunction "C13_14") (pintype "unspecified"))
    )
    (net (code "226") (name "unconnected-(P3-C14-Pad15)") (class "Default")
      (node (ref "P3") (pin "15") (pinfunction "C14_15") (pintype "unspecified"))
    )
    (net (code "227") (name "unconnected-(P3-C15-Pad16)") (class "Default")
      (node (ref "P3") (pin "16") (pinfunction "C15_16") (pintype "unspecified"))
    )
    (net (code "228") (name "unconnected-(P4-C0-Pad1)") (class "Default")
      (node (ref "P4") (pin "1") (pinfunction "C0_1") (pintype "unspecified"))
    )
    (net (code "229") (name "unconnected-(P4-C1-Pad2)") (class "Default")
      (node (ref "P4") (pin "2") (pinfunction "C1_2") (pintype "unspecified"))
    )
    (net (code "230") (name "unconnected-(P4-C2-Pad3)") (class "Default")
      (node (ref "P4") (pin "3") (pinfunction "C2_3") (pintype "unspecified"))
    )
    (net (code "231") (name "unconnected-(P4-C3-Pad4)") (class "Default")
      (node (ref "P4") (pin "4") (pinfunction "C3_4") (pintype "unspecified"))
    )
    (net (code "232") (name "unconnected-(P4-C4-Pad5)") (class "Default")
      (node (ref "P4") (pin "5") (pinfunction "C4_5") (pintype "unspecified"))
    )
    (net (code "233") (name "unconnected-(P4-C5-Pad6)") (class "Default")
      (node (ref "P4") (pin "6") (pinfunction "C5_6") (pintype "unspecified"))
    )
    (net (code "234") (name "unconnected-(P4-C6-Pad7)") (class "Default")
      (node (ref "P4") (pin "7") (pinfunction "C6_7") (pintype "unspecified"))
    )
    (net (code "235") (name "unconnected-(P4-C7-Pad8)") (class "Default")
      (node (ref "P4") (pin "8") (pinfunction "C7_8") (pintype "unspecified"))
    )
    (net (code "236") (name "unconnected-(P4-C8-Pad9)") (class "Default")
      (node (ref "P4") (pin "9") (pinfunction "C8_9") (pintype "unspecified"))
    )
    (net (code "237") (name "unconnected-(P4-C9-Pad10)") (class "Default")
      (node (ref "P4") (pin "10") (pinfunction "C9_10") (pintype "unspecified"))
    )
    (net (code "238") (name "unconnected-(P4-C10-Pad11)") (class "Default")
      (node (ref "P4") (pin "11") (pinfunction "C10_11") (pintype "unspecified"))
    )
    (net (code "239") (name "unconnected-(P4-C11-Pad12)") (class "Default")
      (node (ref "P4") (pin "12") (pinfunction "C11_12") (pintype "unspecified"))
    )
    (net (code "240") (name "unconnected-(P4-C12-Pad13)") (class "Default")
      (node (ref "P4") (pin "13") (pinfunction "C12_13") (pintype "unspecified"))
    )
    (net (code "241") (name "unconnected-(P4-C13-Pad14)") (class "Default")
      (node (ref "P4") (pin "14") (pinfunction "C13_14") (pintype "unspecified"))
    )
    (net (code "242") (name "unconnected-(P4-C14-Pad15)") (class "Default")
      (node (ref "P4") (pin "15") (pinfunction "C14_15") (pintype "unspecified"))
    )
    (net (code "243") (name "unconnected-(P4-C15-Pad16)") (class "Default")
      (node (ref "P4") (pin "16") (pinfunction "C15_16") (pintype "unspecified"))
    )
    (net (code "244") (name "unconnected-(RPI1-3.3V-Pad1)") (class "Default")
      (node (ref "RPI1") (pin "1") (pinfunction "3.3V_1") (pintype "passive"))
    )
    (net (code "245") (name "unconnected-(RPI1-3.3V-Pad17)") (class "Default")
      (node (ref "RPI1") (pin "17") (pinfunction "3.3V_17") (pintype "passive"))
    )
    (net (code "246") (name "unconnected-(RPI1-5V-Pad4)") (class "Default")
      (node (ref "RPI1") (pin "4") (pinfunction "5V_4") (pintype "passive"))
    )
    (net (code "247") (name "unconnected-(RPI1-GND-Pad14)") (class "Default")
      (node (ref "RPI1") (pin "14") (pinfunction "GND_14") (pintype "unspecified"))
    )
    (net (code "248") (name "unconnected-(RPI1-GND-Pad20)") (class "Default")
      (node (ref "RPI1") (pin "20") (pinfunction "GND_20") (pintype "unspecified"))
    )
    (net (code "249") (name "unconnected-(RPI1-GND-Pad25)") (class "Default")
      (node (ref "RPI1") (pin "25") (pinfunction "GND_25") (pintype "unspecified"))
    )
    (net (code "250") (name "unconnected-(RPI1-GND-Pad30)") (class "Default")
      (node (ref "RPI1") (pin "30") (pinfunction "GND_30") (pintype "unspecified"))
    )
    (net (code "251") (name "unconnected-(RPI1-GND-Pad34)") (class "Default")
      (node (ref "RPI1") (pin "34") (pinfunction "GND_34") (pintype "unspecified"))
    )
    (net (code "252") (name "unconnected-(RPI1-GND-Pad39)") (class "Default")
      (node (ref "RPI1") (pin "39") (pinfunction "GND_39") (pintype "unspecified"))
    )
    (net (code "253") (name "unconnected-(RPI1-GPIO0-Pad27)") (class "Default")
      (node (ref "RPI1") (pin "27") (pinfunction "GPIO0_27") (pintype "unspecified"))
    )
    (net (code "254") (name "unconnected-(RPI1-GPIO1-Pad28)") (class "Default")
      (node (ref "RPI1") (pin "28") (pinfunction "GPIO1_28") (pintype "unspecified"))
    )
    (net (code "255") (name "unconnected-(RPI1-GPIO4-Pad7)") (class "Default")
      (node (ref "RPI1") (pin "7") (pinfunction "GPIO4_7") (pintype "bidirectional"))
    )
    (net (code "256") (name "unconnected-(RPI1-GPIO5-Pad29)") (class "Default")
      (node (ref "RPI1") (pin "29") (pinfunction "GPIO5_29") (pintype "bidirectional"))
    )
    (net (code "257") (name "unconnected-(RPI1-GPIO6-Pad31)") (class "Default")
      (node (ref "RPI1") (pin "31") (pinfunction "GPIO6_31") (pintype "bidirectional"))
    )
    (net (code "258") (name "unconnected-(RPI1-GPIO7-Pad26)") (class "Default")
      (node (ref "RPI1") (pin "26") (pinfunction "GPIO7_26") (pintype "bidirectional"))
    )
    (net (code "259") (name "unconnected-(RPI1-GPIO8-Pad24)") (class "Default")
      (node (ref "RPI1") (pin "24") (pinfunction "GPIO8_24") (pintype "bidirectional"))
    )
    (net (code "260") (name "unconnected-(RPI1-GPIO9-Pad21)") (class "Default")
      (node (ref "RPI1") (pin "21") (pinfunction "GPIO9_21") (pintype "bidirectional"))
    )
    (net (code "261") (name "unconnected-(RPI1-GPIO10-Pad19)") (class "Default")
      (node (ref "RPI1") (pin "19") (pinfunction "GPIO10_19") (pintype "bidirectional"))
    )
    (net (code "262") (name "unconnected-(RPI1-GPIO11-Pad23)") (class "Default")
      (node (ref "RPI1") (pin "23") (pinfunction "GPIO11_23") (pintype "bidirectional"))
    )
    (net (code "263") (name "unconnected-(RPI1-GPIO12-Pad32)") (class "Default")
      (node (ref "RPI1") (pin "32") (pinfunction "GPIO12_32") (pintype "bidirectional"))
    )
    (net (code "264") (name "unconnected-(RPI1-GPIO13-Pad33)") (class "Default")
      (node (ref "RPI1") (pin "33") (pinfunction "GPIO13_33") (pintype "bidirectional"))
    )
    (net (code "265") (name "unconnected-(RPI1-GPIO14-Pad8)") (class "Default")
      (node (ref "RPI1") (pin "8") (pinfunction "GPIO14_8") (pintype "bidirectional"))
    )
    (net (code "266") (name "unconnected-(RPI1-GPIO15-Pad10)") (class "Default")
      (node (ref "RPI1") (pin "10") (pinfunction "GPIO15_10") (pintype "bidirectional"))
    )
    (net (code "267") (name "unconnected-(RPI1-GPIO16-Pad36)") (class "Default")
      (node (ref "RPI1") (pin "36") (pinfunction "GPIO16_36") (pintype "bidirectional"))
    )
    (net (code "268") (name "unconnected-(RPI1-GPIO17-Pad11)") (class "Default")
      (node (ref "RPI1") (pin "11") (pinfunction "GPIO17_11") (pintype "bidirectional"))
    )
    (net (code "269") (name "unconnected-(RPI1-GPIO18-Pad12)") (class "Default")
      (node (ref "RPI1") (pin "12") (pinfunction "GPIO18_12") (pintype "bidirectional"))
    )
    (net (code "270") (name "unconnected-(RPI1-GPIO19-Pad35)") (class "Default")
      (node (ref "RPI1") (pin "35") (pinfunction "GPIO19_35") (pintype "bidirectional"))
    )
    (net (code "271") (name "unconnected-(RPI1-GPIO20-Pad38)") (class "Default")
      (node (ref "RPI1") (pin "38") (pinfunction "GPIO20_38") (pintype "bidirectional"))
    )
    (net (code "272") (name "unconnected-(RPI1-GPIO21-Pad40)") (class "Default")
      (node (ref "RPI1") (pin "40") (pinfunction "GPIO21_40") (pintype "bidirectional"))
    )
    (net (code "273") (name "unconnected-(RPI1-GPIO22-Pad15)") (class "Default")
      (node (ref "RPI1") (pin "15") (pinfunction "GPIO22_15") (pintype "bidirectional"))
    )
    (net (code "274") (name "unconnected-(RPI1-GPIO23-Pad16)") (class "Default")
      (node (ref "RPI1") (pin "16") (pinfunction "GPIO23_16") (pintype "bidirectional"))
    )
    (net (code "275") (name "unconnected-(RPI1-GPIO24-Pad18)") (class "Default")
      (node (ref "RPI1") (pin "18") (pinfunction "GPIO24_18") (pintype "bidirectional"))
    )
    (net (code "276") (name "unconnected-(RPI1-GPIO25-Pad22)") (class "Default")
      (node (ref "RPI1") (pin "22") (pinfunction "GPIO25_22") (pintype "bidirectional"))
    )
    (net (code "277") (name "unconnected-(RPI1-GPIO26-Pad37)") (class "Default")
      (node (ref "RPI1") (pin "37") (pinfunction "GPIO26_37") (pintype "bidirectional"))
    )
    (net (code "278") (name "unconnected-(RPI1-GPIO27-Pad13)") (class "Default")
      (node (ref "RPI1") (pin "13") (pinfunction "GPIO27_13") (pintype "bidirectional"))
    )
    (net (code "279") (name "unconnected-(U1-3v3_(OUT)-Pad36)") (class "Default")
      (node (ref "U1") (pin "36") (pinfunction "3v3_(OUT)_36") (pintype "unspecified"))
    )
    (net (code "280") (name "unconnected-(U1-3v3_EN-Pad37)") (class "Default")
      (node (ref "U1") (pin "37") (pinfunction "3v3_EN_37") (pintype "unspecified"))
    )
    (net (code "281") (name "unconnected-(U1-ADC_VREF-Pad35)") (class "Default")
      (node (ref "U1") (pin "35") (pinfunction "ADC_VREF_35") (pintype "unspecified"))
    )
    (net (code "282") (name "unconnected-(U1-GND-Pad8)") (class "Default")
      (node (ref "U1") (pin "8") (pinfunction "GND_8") (pintype "unspecified"))
    )
    (net (code "283") (name "unconnected-(U1-GND-Pad13)") (class "Default")
      (node (ref "U1") (pin "13") (pinfunction "GND_13") (pintype "unspecified"))
    )
    (net (code "284") (name "unconnected-(U1-GND-Pad18)") (class "Default")
      (node (ref "U1") (pin "18") (pinfunction "GND_18") (pintype "unspecified"))
    )
    (net (code "285") (name "unconnected-(U1-GND-Pad23)") (class "Default")
      (node (ref "U1") (pin "23") (pinfunction "GND_23") (pintype "unspecified"))
    )
    (net (code "286") (name "unconnected-(U1-GND-Pad28)") (class "Default")
      (node (ref "U1") (pin "28") (pinfunction "GND_28") (pintype "unspecified"))
    )
    (net (code "287") (name "unconnected-(U1-GND-Pad33)") (class "Default")
      (node (ref "U1") (pin "33") (pinfunction "GND_33") (pintype "unspecified"))
    )
    (net (code "288") (name "unconnected-(U1-GPIO_2-Pad4)") (class "Default")
      (node (ref "U1") (pin "4") (pinfunction "GPIO_2_4") (pintype "unspecified"))
    )
    (net (code "289") (name "unconnected-(U1-GPIO_3-Pad5)") (class "Default")
      (node (ref "U1") (pin "5") (pinfunction "GPIO_3_5") (pintype "unspecified"))
    )
    (net (code "290") (name "unconnected-(U1-GPIO_4-Pad6)") (class "Default")
      (node (ref "U1") (pin "6") (pinfunction "GPIO_4_6") (pintype "unspecified"))
    )
    (net (code "291") (name "unconnected-(U1-GPIO_5-Pad7)") (class "Default")
      (node (ref "U1") (pin "7") (pinfunction "GPIO_5_7") (pintype "unspecified"))
    )
    (net (code "292") (name "unconnected-(U1-GPIO_6-Pad9)") (class "Default")
      (node (ref "U1") (pin "9") (pinfunction "GPIO_6_9") (pintype "unspecified"))
    )
    (net (code "293") (name "unconnected-(U1-GPIO_7-Pad10)") (class "Default")
      (node (ref "U1") (pin "10") (pinfunction "GPIO_7_10") (pintype "unspecified"))
    )
    (net (code "294") (name "unconnected-(U1-GPIO_8-Pad11)") (class "Default")
      (node (ref "U1") (pin "11") (pinfunction "GPIO_8_11") (pintype "unspecified"))
    )
    (net (code "295") (name "unconnected-(U1-GPIO_9-Pad12)") (class "Default")
      (node (ref "U1") (pin "12") (pinfunction "GPIO_9_12") (pintype "unspecified"))
    )
    (net (code "296") (name "unconnected-(U1-GPIO_10-Pad14)") (class "Default")
      (node (ref "U1") (pin "14") (pinfunction "GPIO_10_14") (pintype "unspecified"))
    )
    (net (code "297") (name "unconnected-(U1-GPIO_11-Pad15)") (class "Default")
      (node (ref "U1") (pin "15") (pinfunction "GPIO_11_15") (pintype "unspecified"))
    )
    (net (code "298") (name "unconnected-(U1-GPIO_12-Pad16)") (class "Default")
      (node (ref "U1") (pin "16") (pinfunction "GPIO_12_16") (pintype "unspecified"))
    )
    (net (code "299") (name "unconnected-(U1-GPIO_13-Pad17)") (class "Default")
      (node (ref "U1") (pin "17") (pinfunction "GPIO_13_17") (pintype "unspecified"))
    )
    (net (code "300") (name "unconnected-(U1-GPIO_14-Pad19)") (class "Default")
      (node (ref "U1") (pin "19") (pinfunction "GPIO_14_19") (pintype "unspecified"))
    )
    (net (code "301") (name "unconnected-(U1-GPIO_15-Pad20)") (class "Default")
      (node (ref "U1") (pin "20") (pinfunction "GPIO_15_20") (pintype "unspecified"))
    )
    (net (code "302") (name "unconnected-(U1-GPIO_16-Pad21)") (class "Default")
      (node (ref "U1") (pin "21") (pinfunction "GPIO_16_21") (pintype "unspecified"))
    )
    (net (code "303") (name "unconnected-(U1-GPIO_17-Pad22)") (class "Default")
      (node (ref "U1") (pin "22") (pinfunction "GPIO_17_22") (pintype "unspecified"))
    )
    (net (code "304") (name "unconnected-(U1-GPIO_18-Pad24)") (class "Default")
      (node (ref "U1") (pin "24") (pinfunction "GPIO_18_24") (pintype "unspecified"))
    )
    (net (code "305") (name "unconnected-(U1-GPIO_19-Pad25)") (class "Default")
      (node (ref "U1") (pin "25") (pinfunction "GPIO_19_25") (pintype "unspecified"))
    )
    (net (code "306") (name "unconnected-(U1-GPIO_20-Pad26)") (class "Default")
      (node (ref "U1") (pin "26") (pinfunction "GPIO_20_26") (pintype "unspecified"))
    )
    (net (code "307") (name "unconnected-(U1-GPIO_21-Pad27)") (class "Default")
      (node (ref "U1") (pin "27") (pinfunction "GPIO_21_27") (pintype "unspecified"))
    )
    (net (code "308") (name "unconnected-(U1-GPIO_22-Pad29)") (class "Default")
      (node (ref "U1") (pin "29") (pinfunction "GPIO_22_29") (pintype "unspecified"))
    )
    (net (code "309") (name "unconnected-(U1-GPIO_26-Pad31)") (class "Default")
      (node (ref "U1") (pin "31") (pinfunction "GPIO_26_31") (pintype "unspecified"))
    )
    (net (code "310") (name "unconnected-(U1-GPIO_27-Pad32)") (class "Default")
      (node (ref "U1") (pin "32") (pinfunction "GPIO_27_32") (pintype "unspecified"))
    )
    (net (code "311") (name "unconnected-(U1-GPIO_28-Pad34)") (class "Default")
      (node (ref "U1") (pin "34") (pinfunction "GPIO_28_34") (pintype "unspecified"))
    )
    (net (code "312") (name "unconnected-(U1-RUN-Pad30)") (class "Default")
      (node (ref "U1") (pin "30") (pinfunction "RUN_30") (pintype "unspecified"))
    )
    (net (code "313") (name "unconnected-(U1-VBUS-Pad40)") (class "Default")
      (node (ref "U1") (pin "40") (pinfunction "VBUS_40") (pintype "unspecified"))
    )
  )
)
